# eth_lan8742a_phy.net
KiCad netlist of a schematic drawn in Altium Designer
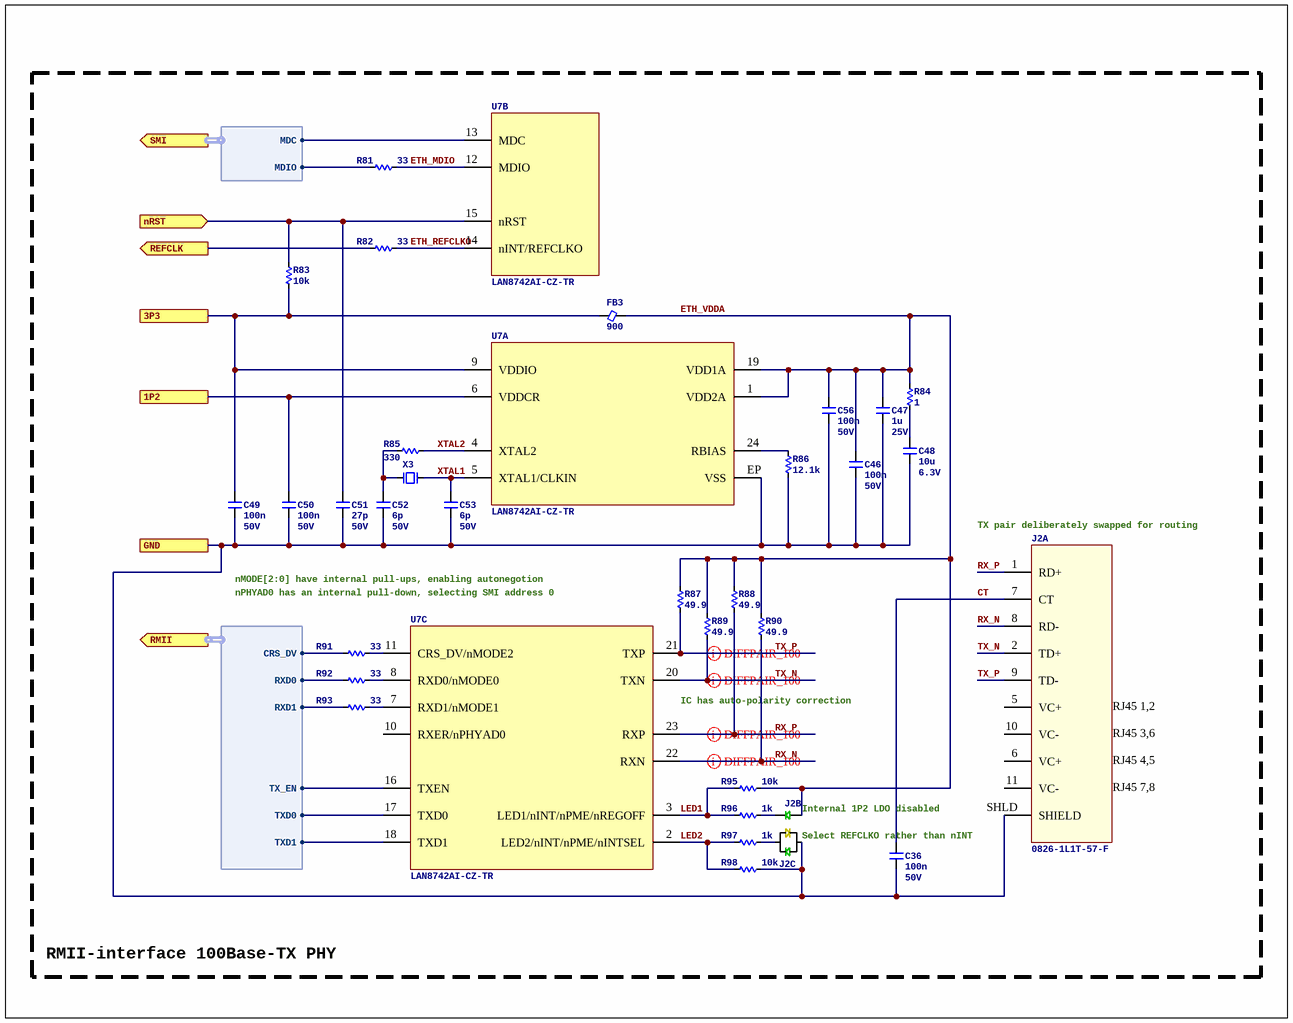
[diagram p0: eth_lan8742a_phy.SchDoc]

(export (version "E")
  (design (tool "Eeschema 10.0.6"))
  (components
    (comp (ref "C36")
      (value "CL05B104KB54PNC")
      (footprint "C0402")
      (fields
        (field (name "CAPACITANCE") "100n")
        (field (name "MANUFACTURER") "Samsung Electro-Mechanics")
        (field (name "VOLTAGE RATING") "50V")
      )
      (libsource (lib "database") (part "__template_cap"))
    )
    (comp (ref "C46")
      (value "CL05B104KB54PNC")
      (footprint "C0402")
      (fields
        (field (name "CAPACITANCE") "100n")
        (field (name "MANUFACTURER") "Samsung Electro-Mechanics")
        (field (name "VOLTAGE RATING") "50V")
      )
      (libsource (lib "database") (part "__template_cap"))
    )
    (comp (ref "C47")
      (value "CL10B105KA8NNNC")
      (footprint "C0603")
      (fields
        (field (name "CAPACITANCE") "1u")
        (field (name "MANUFACTURER") "Samsung Electro-Mechanics")
        (field (name "VOLTAGE RATING") "25V")
      )
      (libsource (lib "database") (part "__template_cap"))
    )
    (comp (ref "C48")
      (value "CC0805KKX7R5BB106")
      (footprint "C0805")
      (fields
        (field (name "CAPACITANCE") "10u")
        (field (name "MANUFACTURER") "YAGEO")
        (field (name "VOLTAGE RATING") "6.3V")
      )
      (libsource (lib "database") (part "__template_cap"))
    )
    (comp (ref "C49")
      (value "CL05B104KB54PNC")
      (footprint "C0402")
      (fields
        (field (name "CAPACITANCE") "100n")
        (field (name "MANUFACTURER") "Samsung Electro-Mechanics")
        (field (name "VOLTAGE RATING") "50V")
      )
      (libsource (lib "database") (part "__template_cap"))
    )
    (comp (ref "C50")
      (value "CL05B104KB54PNC")
      (footprint "C0402")
      (fields
        (field (name "CAPACITANCE") "100n")
        (field (name "MANUFACTURER") "Samsung Electro-Mechanics")
        (field (name "VOLTAGE RATING") "50V")
      )
      (libsource (lib "database") (part "__template_cap"))
    )
    (comp (ref "C51")
      (value "CC0402JRNPO9BN270")
      (footprint "C0402")
      (fields
        (field (name "CAPACITANCE") "27p")
        (field (name "MANUFACTURER") "YAGEO")
        (field (name "VOLTAGE RATING") "50V")
      )
      (libsource (lib "database") (part "__template_cap"))
    )
    (comp (ref "C52")
      (value "CC0402CRNPO9BN6R0")
      (footprint "C0402")
      (fields
        (field (name "CAPACITANCE") "6p")
        (field (name "MANUFACTURER") "YAGEO")
        (field (name "VOLTAGE RATING") "50V")
      )
      (libsource (lib "database") (part "__template_cap"))
    )
    (comp (ref "C53")
      (value "CC0402CRNPO9BN6R0")
      (footprint "C0402")
      (fields
        (field (name "CAPACITANCE") "6p")
        (field (name "MANUFACTURER") "YAGEO")
        (field (name "VOLTAGE RATING") "50V")
      )
      (libsource (lib "database") (part "__template_cap"))
    )
    (comp (ref "C56")
      (value "CL05B104KB54PNC")
      (footprint "C0402")
      (fields
        (field (name "CAPACITANCE") "100n")
        (field (name "MANUFACTURER") "Samsung Electro-Mechanics")
        (field (name "VOLTAGE RATING") "50V")
      )
      (libsource (lib "database") (part "__template_cap"))
    )
    (comp (ref "FB3")
      (value "BLM15PX601SN1D")
      (footprint "FB0402")
      (fields (field (name "MANUFACTURER") "Murata Electronics") (field (name "CURRENT RATING (MA)") "900"))
      (libsource (lib "database") (part "__template_fb"))
    )
    (comp (ref "J2")
      (value "0826-1L1T-57-F")
      (footprint "BELFUSE_0826-1L1T-57-F")
      (description "CONN MAGJACK 1PORT 100 BASE-T")
      (fields (field (name "MANUFACTURER") "Bel Fuse Inc"))
      (libsource (lib "") (part "CONN_BELFUSE_ETHERNET_0826-1L1T-57-F_1"))
    )
    (comp (ref "R81")
      (value "33")
      (footprint "R0402")
      (fields
        (field (name "TOLERANCE") "1%")
        (field (name "MANUFACTURER PART NUMBER") "CRCW040233R0FKED")
        (field (name "MANUFACTURER") "Vishay Intertech")
      )
      (libsource (lib "database") (part "__template_resistor"))
    )
    (comp (ref "R82")
      (value "33")
      (footprint "R0402")
      (fields
        (field (name "TOLERANCE") "1%")
        (field (name "MANUFACTURER PART NUMBER") "CRCW040233R0FKED")
        (field (name "MANUFACTURER") "Vishay Intertech")
      )
      (libsource (lib "database") (part "__template_resistor"))
    )
    (comp (ref "R83")
      (value "10k")
      (footprint "R0402")
      (fields
        (field (name "TOLERANCE") "1%")
        (field (name "MANUFACTURER PART NUMBER") "0402WGF1002TCE")
        (field (name "MANUFACTURER") "UNI-ROYAL(Uniroyal Elec)")
      )
      (libsource (lib "database") (part "__template_resistor"))
    )
    (comp (ref "R84")
      (value "1")
      (footprint "R0402")
      (fields
        (field (name "TOLERANCE") "1%")
        (field (name "MANUFACTURER PART NUMBER") "CRCW04021R00FKEDC")
        (field (name "MANUFACTURER") "Vishay Intertech")
      )
      (libsource (lib "database") (part "__template_resistor"))
    )
    (comp (ref "R85")
      (value "330")
      (footprint "R0402")
      (fields
        (field (name "TOLERANCE") "1%")
        (field (name "MANUFACTURER PART NUMBER") "0402WGF3300TCE")
        (field (name "MANUFACTURER") "UNI-ROYAL(Uniroyal Elec)")
      )
      (libsource (lib "database") (part "__template_resistor"))
    )
    (comp (ref "R86")
      (value "12.1k")
      (footprint "R0402")
      (fields
        (field (name "TOLERANCE") "1%")
        (field (name "MANUFACTURER PART NUMBER") "RC0402FR-0712K1L")
        (field (name "MANUFACTURER") "YAGEO")
      )
      (libsource (lib "database") (part "__template_resistor"))
    )
    (comp (ref "R87")
      (value "49.9")
      (footprint "R0402")
      (fields
        (field (name "TOLERANCE") "1%")
        (field (name "MANUFACTURER PART NUMBER") "0402WGF499JTCE")
        (field (name "MANUFACTURER") "UNI-ROYAL(Uniroyal Elec)")
      )
      (libsource (lib "database") (part "__template_resistor"))
    )
    (comp (ref "R88")
      (value "49.9")
      (footprint "R0402")
      (fields
        (field (name "TOLERANCE") "1%")
        (field (name "MANUFACTURER PART NUMBER") "0402WGF499JTCE")
        (field (name "MANUFACTURER") "UNI-ROYAL(Uniroyal Elec)")
      )
      (libsource (lib "database") (part "__template_resistor"))
    )
    (comp (ref "R89")
      (value "49.9")
      (footprint "R0402")
      (fields
        (field (name "TOLERANCE") "1%")
        (field (name "MANUFACTURER PART NUMBER") "0402WGF499JTCE")
        (field (name "MANUFACTURER") "UNI-ROYAL(Uniroyal Elec)")
      )
      (libsource (lib "database") (part "__template_resistor"))
    )
    (comp (ref "R90")
      (value "49.9")
      (footprint "R0402")
      (fields
        (field (name "TOLERANCE") "1%")
        (field (name "MANUFACTURER PART NUMBER") "0402WGF499JTCE")
        (field (name "MANUFACTURER") "UNI-ROYAL(Uniroyal Elec)")
      )
      (libsource (lib "database") (part "__template_resistor"))
    )
    (comp (ref "R91")
      (value "33")
      (footprint "R0402")
      (fields
        (field (name "TOLERANCE") "1%")
        (field (name "MANUFACTURER PART NUMBER") "CRCW040233R0FKED")
        (field (name "MANUFACTURER") "Vishay Intertech")
      )
      (libsource (lib "database") (part "__template_resistor"))
    )
    (comp (ref "R92")
      (value "33")
      (footprint "R0402")
      (fields
        (field (name "TOLERANCE") "1%")
        (field (name "MANUFACTURER PART NUMBER") "CRCW040233R0FKED")
        (field (name "MANUFACTURER") "Vishay Intertech")
      )
      (libsource (lib "database") (part "__template_resistor"))
    )
    (comp (ref "R93")
      (value "33")
      (footprint "R0402")
      (fields
        (field (name "TOLERANCE") "1%")
        (field (name "MANUFACTURER PART NUMBER") "CRCW040233R0FKED")
        (field (name "MANUFACTURER") "Vishay Intertech")
      )
      (libsource (lib "database") (part "__template_resistor"))
    )
    (comp (ref "R95")
      (value "10k")
      (footprint "R0402")
      (fields
        (field (name "TOLERANCE") "1%")
        (field (name "MANUFACTURER PART NUMBER") "0402WGF1002TCE")
        (field (name "MANUFACTURER") "UNI-ROYAL(Uniroyal Elec)")
      )
      (libsource (lib "database") (part "__template_resistor"))
    )
    (comp (ref "R96")
      (value "1k")
      (footprint "R0402")
      (fields
        (field (name "TOLERANCE") "1%")
        (field (name "MANUFACTURER PART NUMBER") "0402WGF1001TCE")
        (field (name "MANUFACTURER") "UNI-ROYAL(Uniroyal Elec)")
      )
      (libsource (lib "database") (part "__template_resistor"))
    )
    (comp (ref "R97")
      (value "1k")
      (footprint "R0402")
      (fields
        (field (name "TOLERANCE") "1%")
        (field (name "MANUFACTURER PART NUMBER") "0402WGF1001TCE")
        (field (name "MANUFACTURER") "UNI-ROYAL(Uniroyal Elec)")
      )
      (libsource (lib "database") (part "__template_resistor"))
    )
    (comp (ref "R98")
      (value "10k")
      (footprint "R0402")
      (fields
        (field (name "TOLERANCE") "1%")
        (field (name "MANUFACTURER PART NUMBER") "0402WGF1002TCE")
        (field (name "MANUFACTURER") "UNI-ROYAL(Uniroyal Elec)")
      )
      (libsource (lib "database") (part "__template_resistor"))
    )
    (comp (ref "U7")
      (value "LAN8742AI-CZ-TR")
      (footprint "24QFN4E")
      (description "Ethernet Transceiver, PQCC24")
      (fields (field (name "MANUFACTURER") "Microchip"))
      (libsource (lib "SSCP") (part "ETH_PHY_LAN8742AI"))
    )
    (comp (ref "X3")
      (value "XTAL_XRCGB25M000F3A00R0")
      (footprint "4_SMD_2.0X1.6MM")
      (description "CRYSTAL 25.000MHZ 6PF SMD")
      (fields
        (field (name "MANUFACTURER") "Murata")
        (field (name "MANUFACTURER PART NUMBER") "XRCGB25M000F3A00R0")
      )
      (libsource (lib "SSCP") (part "XTAL_XRCGB25M000F3A00R0"))
    )
  )
  (nets
    (net (code "3") (name "/1P2") (class "Default")
      (node (ref "C50") (pin "1") (pintype "passive"))
      (node (ref "U7") (pin "6") (pinfunction "VDDCR_6") (pintype "passive"))
    )
    (net (code "4") (name "/3P3") (class "Default")
      (node (ref "C49") (pin "1") (pintype "passive"))
      (node (ref "FB3") (pin "1") (pintype "passive"))
      (node (ref "R83") (pin "1") (pintype "passive"))
      (node (ref "U7") (pin "9") (pinfunction "VDDIO_9") (pintype "passive"))
    )
    (net (code "5") (name "/CRS_DV") (class "Default") (node (ref "R91") (pin "2") (pintype "passive")))
    (net (code "6") (name "/CT") (class "Default")
      (node (ref "C36") (pin "1") (pintype "passive"))
      (node (ref "J2") (pin "7") (pinfunction "CT_7") (pintype "passive"))
    )
    (net (code "7") (name "/ETH_MDIO") (class "Default")
      (node (ref "R81") (pin "1") (pintype "passive"))
      (node (ref "U7") (pin "12") (pinfunction "MDIO_12") (pintype "passive"))
    )
    (net (code "8") (name "/ETH_REFCLKO") (class "Default")
      (node (ref "R82") (pin "1") (pintype "passive"))
      (node (ref "U7") (pin "14") (pinfunction "nINT/REFCLKO_14") (pintype "passive"))
    )
    (net (code "9") (name "/ETH_VDDA") (class "Default")
      (node (ref "C46") (pin "1") (pintype "passive"))
      (node (ref "C47") (pin "1") (pintype "passive"))
      (node (ref "C56") (pin "1") (pintype "passive"))
      (node (ref "FB3") (pin "2") (pintype "passive"))
      (node (ref "J2") (pin "15") (pintype "passive"))
      (node (ref "R84") (pin "2") (pintype "passive"))
      (node (ref "R87") (pin "1") (pintype "passive"))
      (node (ref "R88") (pin "1") (pintype "passive"))
      (node (ref "R89") (pin "1") (pintype "passive"))
      (node (ref "R90") (pin "1") (pintype "passive"))
      (node (ref "R95") (pin "2") (pintype "passive"))
      (node (ref "U7") (pin "1") (pinfunction "VDD2A_1") (pintype "passive"))
      (node (ref "U7") (pin "19") (pinfunction "VDD1A_19") (pintype "passive"))
    )
    (net (code "10") (name "/GND") (class "Default")
      (node (ref "C36") (pin "2") (pintype "passive"))
      (node (ref "C46") (pin "2") (pintype "passive"))
      (node (ref "C47") (pin "2") (pintype "passive"))
      (node (ref "C48") (pin "2") (pintype "passive"))
      (node (ref "C49") (pin "2") (pintype "passive"))
      (node (ref "C50") (pin "2") (pintype "passive"))
      (node (ref "C51") (pin "2") (pintype "passive"))
      (node (ref "C52") (pin "2") (pintype "passive"))
      (node (ref "C53") (pin "2") (pintype "passive"))
      (node (ref "C56") (pin "2") (pintype "passive"))
      (node (ref "J2") (pin "13") (pintype "passive"))
      (node (ref "J2") (pin "SHLD") (pinfunction "SHIELD_SHLD") (pintype "passive"))
      (node (ref "R86") (pin "2") (pintype "passive"))
      (node (ref "R98") (pin "2") (pintype "passive"))
      (node (ref "U7") (pin "EP") (pinfunction "VSS_EP") (pintype "passive"))
    )
    (net (code "11") (name "/LED1") (class "Default")
      (node (ref "R95") (pin "1") (pintype "passive"))
      (node (ref "R96") (pin "2") (pintype "passive"))
      (node (ref "U7") (pin "3") (pinfunction "LED1/nINT/nPME/nREGOFF_3") (pintype "passive"))
    )
    (net (code "12") (name "/LED2") (class "Default")
      (node (ref "R97") (pin "2") (pintype "passive"))
      (node (ref "R98") (pin "1") (pintype "passive"))
      (node (ref "U7") (pin "2") (pinfunction "LED2/nINT/nPME/nINTSEL_2") (pintype "passive"))
    )
    (net (code "13") (name "/MDC") (class "Default")
      (node (ref "U7") (pin "13") (pinfunction "MDC_13") (pintype "passive"))
    )
    (net (code "14") (name "/MDIO") (class "Default") (node (ref "R81") (pin "2") (pintype "passive")))
    (net (code "15") (name "/REFCLK") (class "Default") (node (ref "R82") (pin "2") (pintype "passive")))
    (net (code "16") (name "/RXD0") (class "Default") (node (ref "R92") (pin "2") (pintype "passive")))
    (net (code "17") (name "/RXD1") (class "Default") (node (ref "R93") (pin "2") (pintype "passive")))
    (net (code "18") (name "/RX_N") (class "Default")
      (node (ref "J2") (pin "8") (pinfunction "RD-_8") (pintype "passive"))
      (node (ref "R90") (pin "2") (pintype "passive"))
      (node (ref "U7") (pin "22") (pinfunction "RXN_22") (pintype "passive"))
    )
    (net (code "19") (name "/RX_P") (class "Default")
      (node (ref "J2") (pin "1") (pinfunction "RD+_1") (pintype "passive"))
      (node (ref "R88") (pin "2") (pintype "passive"))
      (node (ref "U7") (pin "23") (pinfunction "RXP_23") (pintype "passive"))
    )
    (net (code "20") (name "/TXD0") (class "Default")
      (node (ref "U7") (pin "17") (pinfunction "TXD0_17") (pintype "passive"))
    )
    (net (code "21") (name "/TXD1") (class "Default")
      (node (ref "U7") (pin "18") (pinfunction "TXD1_18") (pintype "passive"))
    )
    (net (code "22") (name "/TX_EN") (class "Default")
      (node (ref "U7") (pin "16") (pinfunction "TXEN_16") (pintype "passive"))
    )
    (net (code "23") (name "/TX_N") (class "Default")
      (node (ref "J2") (pin "2") (pinfunction "TD+_2") (pintype "passive"))
      (node (ref "R89") (pin "2") (pintype "passive"))
      (node (ref "U7") (pin "20") (pinfunction "TXN_20") (pintype "passive"))
    )
    (net (code "24") (name "/TX_P") (class "Default")
      (node (ref "J2") (pin "9") (pinfunction "TD-_9") (pintype "passive"))
      (node (ref "R87") (pin "2") (pintype "passive"))
      (node (ref "U7") (pin "21") (pinfunction "TXP_21") (pintype "passive"))
    )
    (net (code "25") (name "/XTAL1") (class "Default")
      (node (ref "C53") (pin "1") (pintype "passive"))
      (node (ref "U7") (pin "5") (pinfunction "XTAL1/CLKIN_5") (pintype "passive"))
      (node (ref "X3") (pin "1") (pinfunction "1_1") (pintype "passive"))
    )
    (net (code "26") (name "/XTAL2") (class "Default")
      (node (ref "R85") (pin "2") (pintype "passive"))
      (node (ref "U7") (pin "4") (pinfunction "XTAL2_4") (pintype "passive"))
    )
    (net (code "27") (name "/nRST") (class "Default")
      (node (ref "C51") (pin "1") (pintype "passive"))
      (node (ref "R83") (pin "2") (pintype "passive"))
      (node (ref "U7") (pin "15") (pinfunction "nRST_15") (pintype "passive"))
    )
    (net (code "30") (name "Net-(C48-Pad1)") (class "Default")
      (node (ref "C48") (pin "1") (pintype "passive"))
      (node (ref "R84") (pin "1") (pintype "passive"))
    )
    (net (code "31") (name "Net-(C52-Pad1)") (class "Default")
      (node (ref "C52") (pin "1") (pintype "passive"))
      (node (ref "R85") (pin "1") (pintype "passive"))
      (node (ref "X3") (pin "3") (pinfunction "3_3") (pintype "passive"))
    )
    (net (code "32") (name "Net-(J2-Pad12)") (class "Default")
      (node (ref "J2") (pin "12") (pintype "passive"))
      (node (ref "R97") (pin "1") (pintype "passive"))
    )
    (net (code "33") (name "Net-(J2-Pad14)") (class "Default")
      (node (ref "J2") (pin "14") (pintype "passive"))
      (node (ref "R96") (pin "1") (pintype "passive"))
    )
    (net (code "34") (name "Net-(U7A-RBIAS)") (class "Default")
      (node (ref "R86") (pin "1") (pintype "passive"))
      (node (ref "U7") (pin "24") (pinfunction "RBIAS_24") (pintype "passive"))
    )
    (net (code "35") (name "Net-(U7C-CRS_DV{slash}nMODE2)") (class "Default")
      (node (ref "R91") (pin "1") (pintype "passive"))
      (node (ref "U7") (pin "11") (pinfunction "CRS_DV/nMODE2_11") (pintype "passive"))
    )
    (net (code "36") (name "Net-(U7C-RXD0{slash}nMODE0)") (class "Default")
      (node (ref "R92") (pin "1") (pintype "passive"))
      (node (ref "U7") (pin "8") (pinfunction "RXD0/nMODE0_8") (pintype "passive"))
    )
    (net (code "37") (name "Net-(U7C-RXD1{slash}nMODE1)") (class "Default")
      (node (ref "R93") (pin "1") (pintype "passive"))
      (node (ref "U7") (pin "7") (pinfunction "RXD1/nMODE1_7") (pintype "passive"))
    )
    (net (code "38") (name "unconnected-(J2A-VC+-Pad5)") (class "Default")
      (node (ref "J2") (pin "5") (pinfunction "VC+_5") (pintype "passive"))
    )
    (net (code "39") (name "unconnected-(J2A-VC+-Pad6)") (class "Default")
      (node (ref "J2") (pin "6") (pinfunction "VC+_6") (pintype "passive"))
    )
    (net (code "40") (name "unconnected-(J2A-VC--Pad10)") (class "Default")
      (node (ref "J2") (pin "10") (pinfunction "VC-_10") (pintype "passive"))
    )
    (net (code "41") (name "unconnected-(J2A-VC--Pad11)") (class "Default")
      (node (ref "J2") (pin "11") (pinfunction "VC-_11") (pintype "passive"))
    )
    (net (code "42") (name "unconnected-(U7C-RXER{slash}nPHYAD0-Pad10)") (class "Default")
      (node (ref "U7") (pin "10") (pinfunction "RXER/nPHYAD0_10") (pintype "passive"))
    )
  )
)
